# MicroMultimeter_EXP_Sch.net
KiCad netlist of a schematic drawn in Altium Designer
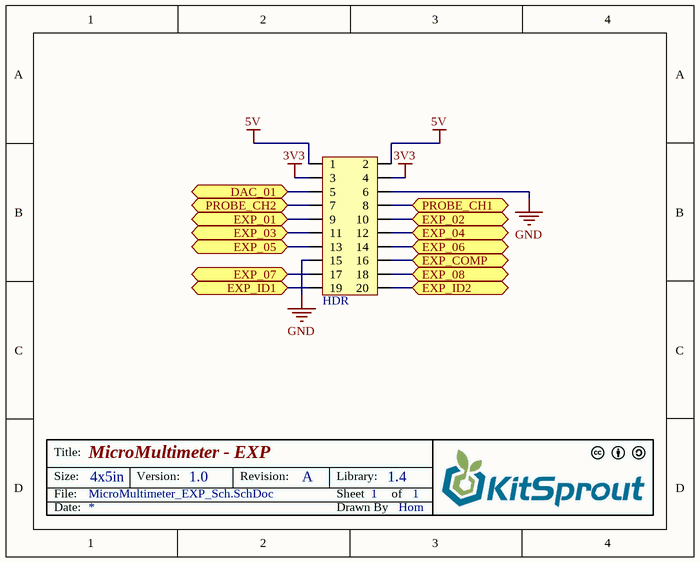
[diagram p0: MicroMultimeter_EXP_Sch.SchDoc]

(export (version "E")
  (design (tool "Eeschema 10.0.6"))
  (components
    (comp (ref "HDR")
      (value "HDR2x10_2.54")
      (footprint "PCB_ConnectorHDR:HDR2X10_2.54_180HF")
      (description "Header")
      (libsource (lib "SCH_ConnectorHDR") (part "HDR2x10_2.54"))
    )
  )
  (nets
    (net (code "1") (name "/DAC_01") (class "Default")
      (node (ref "HDR") (pin "5") (pinfunction "5_5") (pintype "passive"))
    )
    (net (code "2") (name "/EXP_01") (class "Default")
      (node (ref "HDR") (pin "9") (pinfunction "9_9") (pintype "passive"))
    )
    (net (code "3") (name "/EXP_02") (class "Default")
      (node (ref "HDR") (pin "10") (pinfunction "10_10") (pintype "passive"))
    )
    (net (code "4") (name "/EXP_03") (class "Default")
      (node (ref "HDR") (pin "11") (pinfunction "11_11") (pintype "passive"))
    )
    (net (code "5") (name "/EXP_04") (class "Default")
      (node (ref "HDR") (pin "12") (pinfunction "12_12") (pintype "passive"))
    )
    (net (code "6") (name "/EXP_05") (class "Default")
      (node (ref "HDR") (pin "13") (pinfunction "13_13") (pintype "passive"))
    )
    (net (code "7") (name "/EXP_06") (class "Default")
      (node (ref "HDR") (pin "14") (pinfunction "14_14") (pintype "passive"))
    )
    (net (code "8") (name "/EXP_07") (class "Default")
      (node (ref "HDR") (pin "17") (pinfunction "17_17") (pintype "passive"))
    )
    (net (code "9") (name "/EXP_08") (class "Default")
      (node (ref "HDR") (pin "18") (pinfunction "18_18") (pintype "passive"))
    )
    (net (code "10") (name "/EXP_COMP") (class "Default")
      (node (ref "HDR") (pin "16") (pinfunction "16_16") (pintype "passive"))
    )
    (net (code "11") (name "/EXP_ID1") (class "Default")
      (node (ref "HDR") (pin "19") (pinfunction "19_19") (pintype "passive"))
    )
    (net (code "12") (name "/EXP_ID2") (class "Default")
      (node (ref "HDR") (pin "20") (pinfunction "20_20") (pintype "passive"))
    )
    (net (code "13") (name "/PROBE_CH1") (class "Default")
      (node (ref "HDR") (pin "8") (pinfunction "8_8") (pintype "passive"))
    )
    (net (code "14") (name "/PROBE_CH2") (class "Default")
      (node (ref "HDR") (pin "7") (pinfunction "7_7") (pintype "passive"))
    )
    (net (code "15") (name "3V3") (class "Default")
      (node (ref "HDR") (pin "3") (pinfunction "3_3") (pintype "passive"))
      (node (ref "HDR") (pin "4") (pinfunction "4_4") (pintype "passive"))
    )
    (net (code "16") (name "5V") (class "Default")
      (node (ref "HDR") (pin "1") (pinfunction "1_1") (pintype "passive"))
      (node (ref "HDR") (pin "2") (pinfunction "2_2") (pintype "passive"))
    )
    (net (code "17") (name "GND") (class "Default")
      (node (ref "HDR") (pin "15") (pinfunction "15_15") (pintype "passive"))
      (node (ref "HDR") (pin "6") (pinfunction "6_6") (pintype "passive"))
    )
  )
)
